# 05pwr_input.net
KiCad netlist of a schematic drawn in Altium Designer
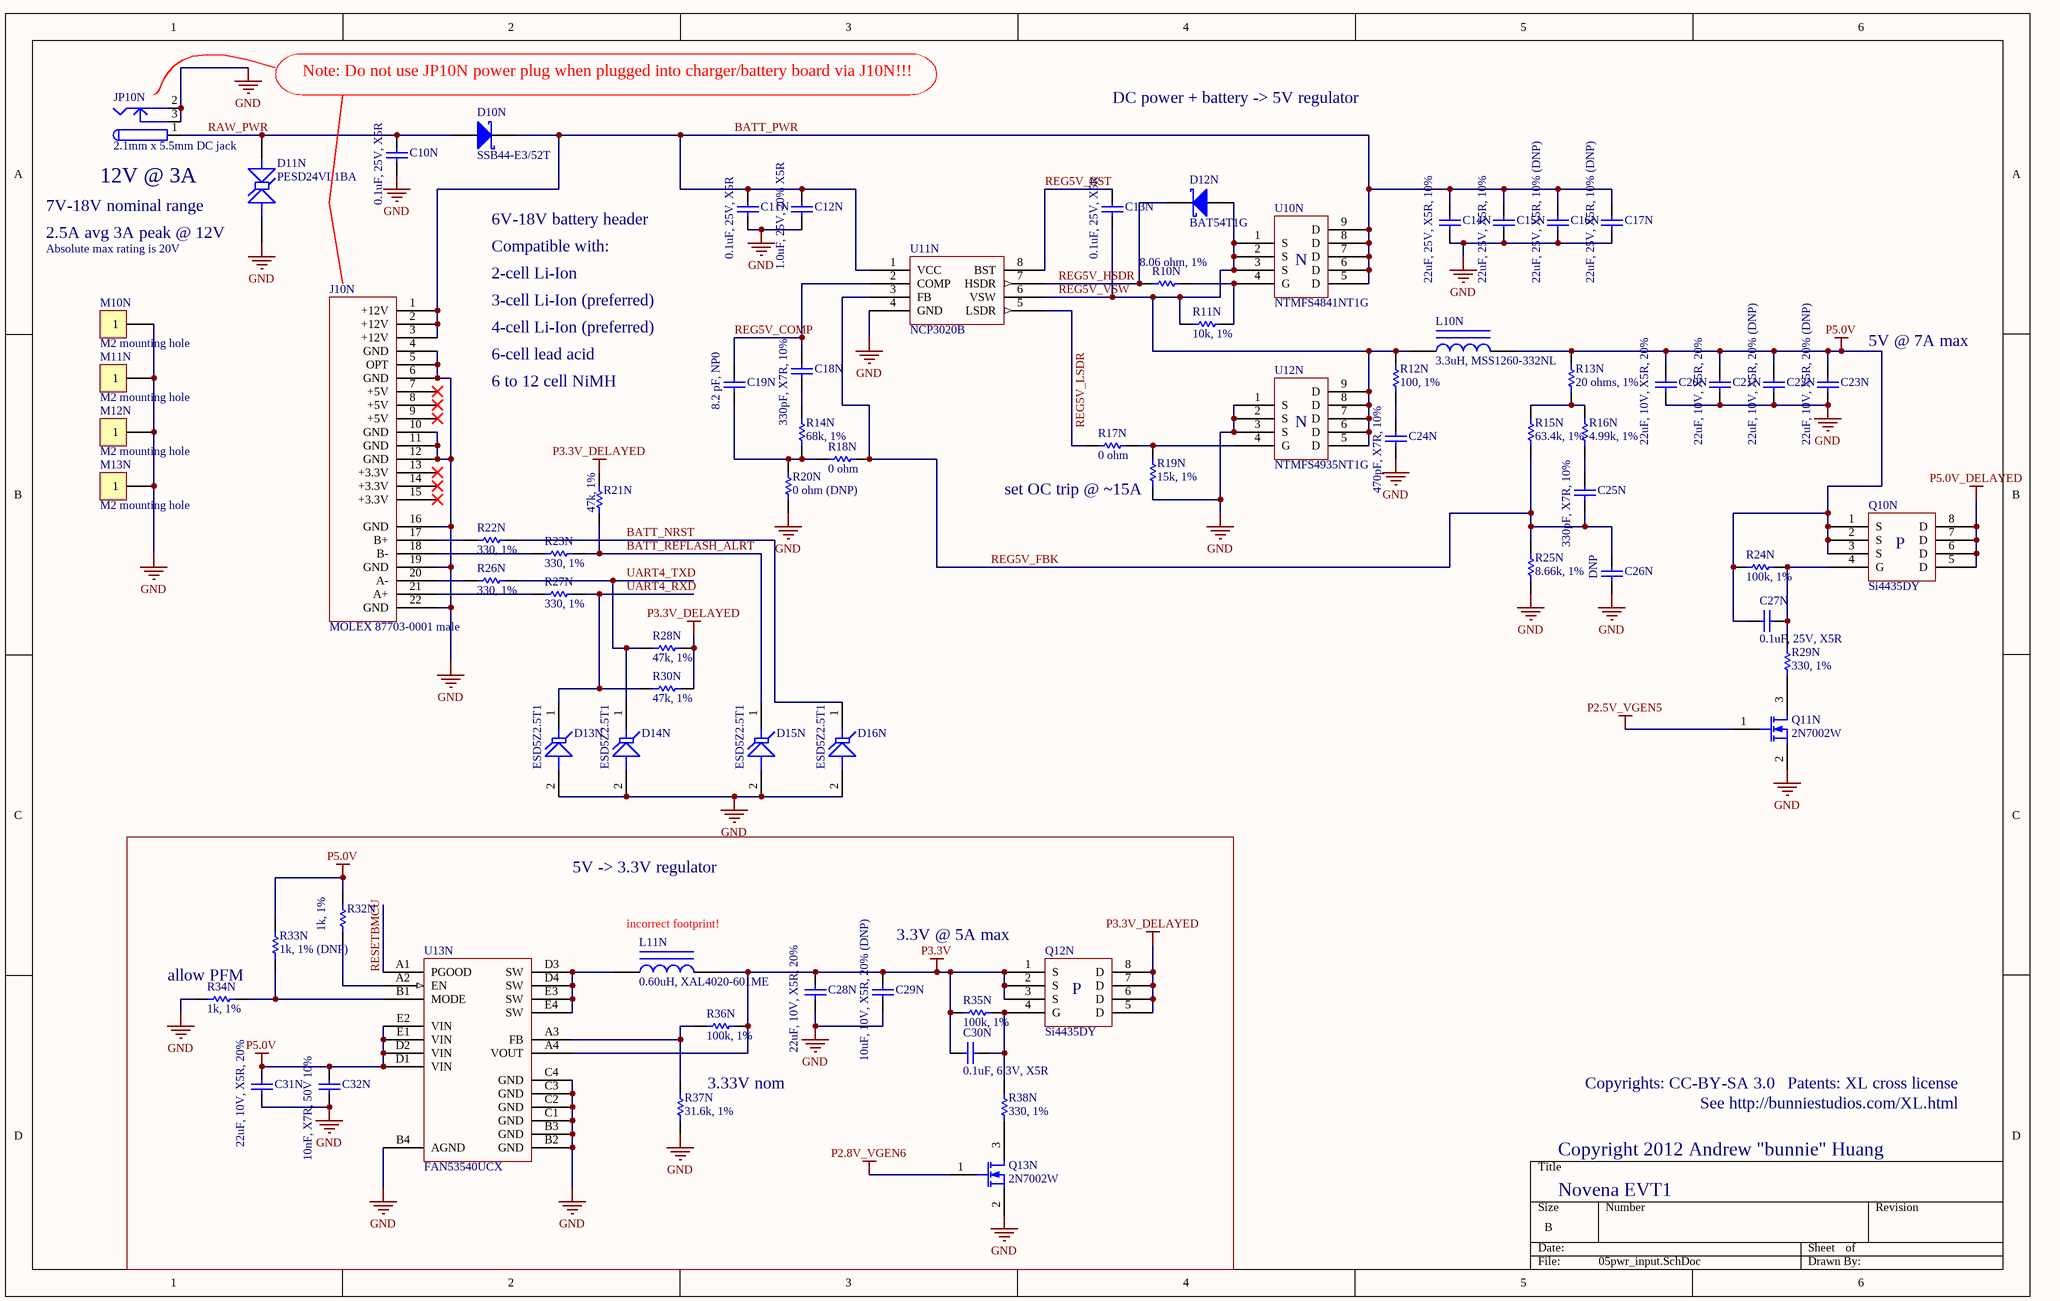
[diagram p0: 05pwr_input.SchDoc]

(export (version "E")
  (design (tool "Eeschema 10.0.6"))
  (components
    (comp (ref "C10N")
      (value "0.1uF, 25V, X5R")
      (footprint "CAPC1005N")
      (description "Capacitor (Semiconductor SIM Model)")
      (fields (field (name "PUBLISHER") "Altium Limited"))
      (libsource (lib "Miscellaneous Devices") (part "Cap Semi"))
    )
    (comp (ref "C11N")
      (value "0.1uF, 25V, X5R")
      (footprint "CAPC1005N")
      (description "Capacitor (Semiconductor SIM Model)")
      (fields (field (name "PUBLISHER") "Altium Limited"))
      (libsource (lib "Miscellaneous Devices") (part "Cap Semi"))
    )
    (comp (ref "C12N")
      (value "1.0uF, 25V, 20% X5R")
      (footprint "CAPC1608N")
      (description "Capacitor (Semiconductor SIM Model)")
      (fields (field (name "PUBLISHER") "Altium Limited"))
      (libsource (lib "Miscellaneous Devices") (part "Cap Semi"))
    )
    (comp (ref "C13N")
      (value "0.1uF, 25V, X5R")
      (footprint "CAPC1005N")
      (description "Capacitor (Semiconductor SIM Model)")
      (fields (field (name "PUBLISHER") "Altium Limited"))
      (libsource (lib "Miscellaneous Devices") (part "Cap Semi"))
    )
    (comp (ref "C14N")
      (value "22uF, 25V, X5R, 10%")
      (footprint "CAPC3225N")
      (description "Capacitor (Semiconductor SIM Model)")
      (fields (field (name "PUBLISHER") "Altium Limited"))
      (libsource (lib "Miscellaneous Devices") (part "Cap Semi"))
    )
    (comp (ref "C15N")
      (value "22uF, 25V, X5R, 10%")
      (footprint "CAPC3225N")
      (description "Capacitor (Semiconductor SIM Model)")
      (fields (field (name "PUBLISHER") "Altium Limited"))
      (libsource (lib "Miscellaneous Devices") (part "Cap Semi"))
    )
    (comp (ref "C16N")
      (value "22uF, 25V, X5R, 10% (DNP)")
      (footprint "CAPC3225N")
      (description "Capacitor (Semiconductor SIM Model)")
      (fields (field (name "PUBLISHER") "Altium Limited"))
      (libsource (lib "Miscellaneous Devices") (part "Cap Semi"))
    )
    (comp (ref "C17N")
      (value "22uF, 25V, X5R, 10% (DNP)")
      (footprint "CAPC3225N")
      (description "Capacitor (Semiconductor SIM Model)")
      (fields (field (name "PUBLISHER") "Altium Limited"))
      (libsource (lib "Miscellaneous Devices") (part "Cap Semi"))
    )
    (comp (ref "C18N")
      (value "330pF, X7R, 10%")
      (footprint "CAPC1005N")
      (description "Capacitor (Semiconductor SIM Model)")
      (fields (field (name "PUBLISHER") "Altium Limited"))
      (libsource (lib "Miscellaneous Devices") (part "Cap Semi"))
    )
    (comp (ref "C19N")
      (value "8.2 pF, NP0")
      (footprint "CAPC1005N")
      (description "Capacitor (Semiconductor SIM Model)")
      (fields (field (name "PUBLISHER") "Altium Limited"))
      (libsource (lib "Miscellaneous Devices") (part "Cap Semi"))
    )
    (comp (ref "C20N")
      (value "22uF, 10V, X5R, 20%")
      (footprint "CAPC2012N")
      (description "Capacitor (Semiconductor SIM Model)")
      (fields (field (name "PUBLISHER") "Altium Limited"))
      (libsource (lib "Miscellaneous Devices") (part "Cap Semi"))
    )
    (comp (ref "C21N")
      (value "22uF, 10V, X5R, 20%")
      (footprint "CAPC2012N")
      (description "Capacitor (Semiconductor SIM Model)")
      (fields (field (name "PUBLISHER") "Altium Limited"))
      (libsource (lib "Miscellaneous Devices") (part "Cap Semi"))
    )
    (comp (ref "C22N")
      (value "22uF, 10V, X5R, 20% (DNP)")
      (footprint "CAPC2012N")
      (description "Capacitor (Semiconductor SIM Model)")
      (fields (field (name "PUBLISHER") "Altium Limited"))
      (libsource (lib "Miscellaneous Devices") (part "Cap Semi"))
    )
    (comp (ref "C23N")
      (value "22uF, 10V, X5R, 20% (DNP)")
      (footprint "CAPC2012N")
      (description "Capacitor (Semiconductor SIM Model)")
      (fields (field (name "PUBLISHER") "Altium Limited"))
      (libsource (lib "Miscellaneous Devices") (part "Cap Semi"))
    )
    (comp (ref "C24N")
      (value "470pF, X7R, 10%")
      (footprint "CAPC1005N")
      (description "Capacitor (Semiconductor SIM Model)")
      (fields (field (name "PUBLISHER") "Altium Limited"))
      (libsource (lib "Miscellaneous Devices") (part "Cap Semi"))
    )
    (comp (ref "C25N")
      (value "330pF, X7R, 10%")
      (footprint "CAPC1005N")
      (description "Capacitor (Semiconductor SIM Model)")
      (fields (field (name "PUBLISHER") "Altium Limited"))
      (libsource (lib "Miscellaneous Devices") (part "Cap Semi"))
    )
    (comp (ref "C26N")
      (value "DNP")
      (footprint "CAPC1005N")
      (description "Capacitor (Semiconductor SIM Model)")
      (fields (field (name "PUBLISHER") "Altium Limited"))
      (libsource (lib "Miscellaneous Devices") (part "Cap Semi"))
    )
    (comp (ref "C27N")
      (value "0.1uF, 25V, X5R")
      (footprint "CAPC1005N")
      (description "Capacitor (Semiconductor SIM Model)")
      (fields (field (name "PUBLISHER") "Altium Limited"))
      (libsource (lib "Miscellaneous Devices") (part "Cap Semi"))
    )
    (comp (ref "C28N")
      (value "22uF, 10V, X5R, 20%")
      (footprint "CAPC2012N")
      (description "Capacitor (Semiconductor SIM Model)")
      (fields (field (name "PUBLISHER") "Altium Limited"))
      (libsource (lib "Miscellaneous Devices") (part "Cap Semi"))
    )
    (comp (ref "C29N")
      (value "10uF, 10V, X5R, 20% (DNP)")
      (footprint "CAPC1608N")
      (description "Capacitor (Semiconductor SIM Model)")
      (fields (field (name "PUBLISHER") "Altium Limited"))
      (libsource (lib "Miscellaneous Devices") (part "Cap Semi"))
    )
    (comp (ref "C30N")
      (value "0.1uF, 6.3V, X5R")
      (footprint "CAPC0603N_B")
      (description "Capacitor (Semiconductor SIM Model)")
      (fields (field (name "PUBLISHER") "Altium Limited"))
      (libsource (lib "Miscellaneous Devices") (part "Cap Semi"))
    )
    (comp (ref "C31N")
      (value "22uF, 10V, X5R, 20%")
      (footprint "CAPC2012N")
      (description "Capacitor (Semiconductor SIM Model)")
      (fields (field (name "PUBLISHER") "Altium Limited"))
      (libsource (lib "Miscellaneous Devices") (part "Cap Semi"))
    )
    (comp (ref "C32N")
      (value "10nF, X7R, 50V 10%")
      (footprint "CAPC1005N")
      (description "Capacitor (Semiconductor SIM Model)")
      (fields (field (name "PUBLISHER") "Altium Limited"))
      (libsource (lib "Miscellaneous Devices") (part "Cap Semi"))
    )
    (comp (ref "D10N")
      (value "SSB44-E3/52T")
      (footprint "DSO-C2/X2.3")
      (description "Schottky Diode")
      (fields (field (name "PUBLISHER") "Altium Limited"))
      (libsource (lib "Miscellaneous Devices") (part "D Schottky"))
    )
    (comp (ref "D11N")
      (value "PESD24VL1BA")
      (footprint "SOD-323")
      (description "Bidirectional zener diode, Vz 17.1V nom")
      (libsource (lib "commonsch") (part "BIDIR_ESD"))
    )
    (comp (ref "D12N")
      (value "BAT54T1G")
      (footprint "SOD123")
      (description "Schottky Diode")
      (fields (field (name "PUBLISHER") "Altium Limited"))
      (libsource (lib "Miscellaneous Devices") (part "D Schottky"))
    )
    (comp (ref "D13N")
      (value "ESD5Z2.5T1")
      (footprint "SOD-523")
      (description "On Semi 3.3V standoff TVS diode")
      (fields (field (name "PUBLISHER") "Altium Limited"))
      (libsource (lib "Miscellaneous Devices") (part "Tranzorb"))
    )
    (comp (ref "D14N")
      (value "ESD5Z2.5T1")
      (footprint "SOD-523")
      (description "On Semi 3.3V standoff TVS diode")
      (fields (field (name "PUBLISHER") "Altium Limited"))
      (libsource (lib "Miscellaneous Devices") (part "Tranzorb"))
    )
    (comp (ref "D15N")
      (value "ESD5Z2.5T1")
      (footprint "SOD-523")
      (description "On Semi 3.3V standoff TVS diode")
      (fields (field (name "PUBLISHER") "Altium Limited"))
      (libsource (lib "Miscellaneous Devices") (part "Tranzorb"))
    )
    (comp (ref "D16N")
      (value "ESD5Z2.5T1")
      (footprint "SOD-523")
      (description "On Semi 3.3V standoff TVS diode")
      (fields (field (name "PUBLISHER") "Altium Limited"))
      (libsource (lib "Miscellaneous Devices") (part "Tranzorb"))
    )
    (comp (ref "J10N")
      (value "MOLEX 87703-0001 male")
      (footprint "SATA_MOLEX-87703-0001")
      (description "SATA+Power connector")
      (libsource (lib "commonsch") (part "SATA_22P_HEADER"))
    )
    (comp (ref "JP10N")
      (value "2.1mm x 5.5mm DC jack")
      (footprint "CUI_PJ_002AH_SMT")
      (description "Low Voltage Power Supply Connector")
      (fields (field (name "PUBLISHER") "Altium Limited"))
      (libsource (lib "Miscellaneous Connectors") (part "PWR2.5"))
    )
    (comp (ref "L10N")
      (value "3.3uH, MSS1260-332NL")
      (footprint "COILCRAFT_MSS1048")
      (description "Magnetic-Core Inductor")
      (fields (field (name "PUBLISHER") "Altium Limited"))
      (libsource (lib "Miscellaneous Devices") (part "Inductor Iron"))
    )
    (comp (ref "L11N")
      (value "0.60uH, XAL4020-601ME")
      (footprint "COILCRAFT_MSS1048")
      (description "Magnetic-Core Inductor")
      (fields (field (name "PUBLISHER") "Altium Limited"))
      (libsource (lib "Miscellaneous Devices") (part "Inductor Iron"))
    )
    (comp (ref "M10N")
      (value "M2 mounting hole")
      (footprint "HOLE_M2_MOUNT")
      (description "Connector")
      (libsource (lib "*") (part "CON1"))
    )
    (comp (ref "M11N")
      (value "M2 mounting hole")
      (footprint "HOLE_M2_MOUNT")
      (description "Connector")
      (libsource (lib "*") (part "CON1"))
    )
    (comp (ref "M12N")
      (value "M2 mounting hole")
      (footprint "HOLE_M2_MOUNT")
      (description "Connector")
      (libsource (lib "*") (part "CON1"))
    )
    (comp (ref "M13N")
      (value "M2 mounting hole")
      (footprint "HOLE_M2_MOUNT")
      (description "Connector")
      (libsource (lib "*") (part "CON1"))
    )
    (comp (ref "Q10N")
      (value "Si4435DY")
      (footprint "SOIC127P600-8AN")
      (description "Singre P-channel FET, 8A, 30V")
      (libsource (lib "commonsch") (part "Si4435DY"))
    )
    (comp (ref "Q11N")
      (value "2N7002W")
      (footprint "SOT323-3AN")
      (description "N-Channel MOSFET")
      (fields (field (name "PUBLISHER") "Altium Limited"))
      (libsource (lib "Miscellaneous Devices") (part "MOSFET-N"))
    )
    (comp (ref "Q12N")
      (value "Si4435DY")
      (footprint "SOIC127P600-8AN")
      (description "Singre P-channel FET, 8A, 30V")
      (libsource (lib "commonsch") (part "Si4435DY"))
    )
    (comp (ref "Q13N")
      (value "2N7002W")
      (footprint "SOT323-3AN")
      (description "N-Channel MOSFET")
      (fields (field (name "PUBLISHER") "Altium Limited"))
      (libsource (lib "Miscellaneous Devices") (part "MOSFET-N"))
    )
    (comp (ref "R10N")
      (value "8.06 ohm, 1%")
      (footprint "RESC1005N")
      (description "Resistor")
      (fields (field (name "PUBLISHER") "Altium Limited"))
      (libsource (lib "Miscellaneous Devices") (part "Res1"))
    )
    (comp (ref "R11N")
      (value "10k, 1%")
      (footprint "RESC1005N")
      (description "Resistor")
      (fields (field (name "PUBLISHER") "Altium Limited"))
      (libsource (lib "Miscellaneous Devices") (part "Res1"))
    )
    (comp (ref "R12N")
      (value "100, 1%")
      (footprint "RESC1005N")
      (description "Resistor")
      (fields (field (name "PUBLISHER") "Altium Limited"))
      (libsource (lib "Miscellaneous Devices") (part "Res1"))
    )
    (comp (ref "R13N")
      (value "20 ohms, 1%")
      (footprint "RESC1005N")
      (description "Resistor")
      (fields (field (name "PUBLISHER") "Altium Limited"))
      (libsource (lib "Miscellaneous Devices") (part "Res1"))
    )
    (comp (ref "R14N")
      (value "68k, 1%")
      (footprint "RESC1005N")
      (description "Resistor")
      (fields (field (name "PUBLISHER") "Altium Limited"))
      (libsource (lib "Miscellaneous Devices") (part "Res1"))
    )
    (comp (ref "R15N")
      (value "63.4k, 1%")
      (footprint "RESC1005N")
      (description "Resistor")
      (fields (field (name "PUBLISHER") "Altium Limited"))
      (libsource (lib "Miscellaneous Devices") (part "Res1"))
    )
    (comp (ref "R16N")
      (value "4.99k, 1%")
      (footprint "RESC1005N")
      (description "Resistor")
      (fields (field (name "PUBLISHER") "Altium Limited"))
      (libsource (lib "Miscellaneous Devices") (part "Res1"))
    )
    (comp (ref "R17N")
      (value "0 ohm")
      (footprint "RESC1005N")
      (description "Resistor")
      (fields (field (name "PUBLISHER") "Altium Limited"))
      (libsource (lib "Miscellaneous Devices") (part "Res1"))
    )
    (comp (ref "R18N")
      (value "0 ohm")
      (footprint "RESC1005N")
      (description "Resistor")
      (fields (field (name "PUBLISHER") "Altium Limited"))
      (libsource (lib "Miscellaneous Devices") (part "Res1"))
    )
    (comp (ref "R19N")
      (value "15k, 1%")
      (footprint "RESC1005N")
      (description "Resistor")
      (fields (field (name "PUBLISHER") "Altium Limited"))
      (libsource (lib "Miscellaneous Devices") (part "Res1"))
    )
    (comp (ref "R20N")
      (value "0 ohm (DNP)")
      (footprint "RESC1005N")
      (description "Resistor")
      (fields (field (name "PUBLISHER") "Altium Limited"))
      (libsource (lib "Miscellaneous Devices") (part "Res1"))
    )
    (comp (ref "R21N")
      (value "47k, 1%")
      (footprint "RESC1005N")
      (description "Resistor")
      (fields (field (name "PUBLISHER") "Altium Limited"))
      (libsource (lib "Miscellaneous Devices") (part "Res1"))
    )
    (comp (ref "R22N")
      (value "330, 1%")
      (footprint "RESC1005N")
      (description "Resistor")
      (fields (field (name "PUBLISHER") "Altium Limited"))
      (libsource (lib "Miscellaneous Devices") (part "Res1"))
    )
    (comp (ref "R23N")
      (value "330, 1%")
      (footprint "RESC1005N")
      (description "Resistor")
      (fields (field (name "PUBLISHER") "Altium Limited"))
      (libsource (lib "Miscellaneous Devices") (part "Res1"))
    )
    (comp (ref "R24N")
      (value "100k, 1%")
      (footprint "RESC1005N")
      (description "Resistor")
      (fields (field (name "PUBLISHER") "Altium Limited"))
      (libsource (lib "Miscellaneous Devices") (part "Res1"))
    )
    (comp (ref "R25N")
      (value "8.66k, 1%")
      (footprint "RESC1005N")
      (description "Resistor")
      (fields (field (name "PUBLISHER") "Altium Limited"))
      (libsource (lib "Miscellaneous Devices") (part "Res1"))
    )
    (comp (ref "R26N")
      (value "330, 1%")
      (footprint "RESC1005N")
      (description "Resistor")
      (fields (field (name "PUBLISHER") "Altium Limited"))
      (libsource (lib "Miscellaneous Devices") (part "Res1"))
    )
    (comp (ref "R27N")
      (value "330, 1%")
      (footprint "RESC1005N")
      (description "Resistor")
      (fields (field (name "PUBLISHER") "Altium Limited"))
      (libsource (lib "Miscellaneous Devices") (part "Res1"))
    )
    (comp (ref "R28N")
      (value "47k, 1%")
      (footprint "RESC1005N")
      (description "Resistor")
      (fields (field (name "PUBLISHER") "Altium Limited"))
      (libsource (lib "Miscellaneous Devices") (part "Res1"))
    )
    (comp (ref "R29N")
      (value "330, 1%")
      (footprint "RESC1005N")
      (description "Resistor")
      (fields (field (name "PUBLISHER") "Altium Limited"))
      (libsource (lib "Miscellaneous Devices") (part "Res1"))
    )
    (comp (ref "R30N")
      (value "47k, 1%")
      (footprint "RESC1005N")
      (description "Resistor")
      (fields (field (name "PUBLISHER") "Altium Limited"))
      (libsource (lib "Miscellaneous Devices") (part "Res1"))
    )
    (comp (ref "R32N")
      (value "1k, 1%")
      (footprint "RESC1005N")
      (description "Resistor")
      (fields (field (name "PUBLISHER") "Altium Limited"))
      (libsource (lib "Miscellaneous Devices") (part "Res1"))
    )
    (comp (ref "R33N")
      (value "1k, 1% (DNP)")
      (footprint "RESC1005N")
      (description "Resistor")
      (fields (field (name "PUBLISHER") "Altium Limited"))
      (libsource (lib "Miscellaneous Devices") (part "Res1"))
    )
    (comp (ref "R34N")
      (value "1k, 1%")
      (footprint "RESC1005N")
      (description "Resistor")
      (fields (field (name "PUBLISHER") "Altium Limited"))
      (libsource (lib "Miscellaneous Devices") (part "Res1"))
    )
    (comp (ref "R35N")
      (value "100k, 1%")
      (footprint "RESC1005N")
      (description "Resistor")
      (fields (field (name "PUBLISHER") "Altium Limited"))
      (libsource (lib "Miscellaneous Devices") (part "Res1"))
    )
    (comp (ref "R36N")
      (value "100k, 1%")
      (footprint "RESC1005N")
      (description "Resistor")
      (fields (field (name "PUBLISHER") "Altium Limited"))
      (libsource (lib "Miscellaneous Devices") (part "Res1"))
    )
    (comp (ref "R37N")
      (value "31.6k, 1%")
      (footprint "RESC1005N")
      (description "Resistor")
      (fields (field (name "PUBLISHER") "Altium Limited"))
      (libsource (lib "Miscellaneous Devices") (part "Res1"))
    )
    (comp (ref "R38N")
      (value "330, 1%")
      (footprint "RESC1005N")
      (description "Resistor")
      (fields (field (name "PUBLISHER") "Altium Limited"))
      (libsource (lib "Miscellaneous Devices") (part "Res1"))
    )
    (comp (ref "U10N")
      (value "NTMFS4841NT1G")
      (footprint "ONSEMI_DFN5_5x6_1.27P")
      (description "N channel power MOSFET, 30V, 57A SO-8FL")
      (libsource (lib "commonsch") (part "NTMFS4841N"))
    )
    (comp (ref "U11N")
      (value "NCP3020B")
      (footprint "SOIC127P600-8AN")
      (description "Synchronous PWM controller, 4.7-28V in, 0.6V ref")
      (libsource (lib "commonsch") (part "NCP3020B"))
    )
    (comp (ref "U12N")
      (value "NTMFS4935NT1G")
      (footprint "ONSEMI_DFN5_5x6_1.27P")
      (description "N channel power MOSFET, 30V, 57A SO-8FL")
      (libsource (lib "commonsch") (part "NTMFS4841N"))
    )
    (comp (ref "U13N")
      (value "FAN53540UCX")
      (footprint "FAIRCHILD_WLCSP_BGA100P9X9-81A")
      (description "2.4MHz 5A Sync buck regulator, integrated FET")
      (libsource (lib "commonsch") (part "FAN53540UCX"))
    )
  )
  (nets
    (net (code "1") (name "/BATT_NRST") (class "Default")
      (node (ref "D16N") (pin "1") (pinfunction "K_1") (pintype "passive"))
      (node (ref "R22N") (pin "2") (pinfunction "2_2") (pintype "passive"))
    )
    (net (code "2") (name "/BATT_PWR") (class "Default")
      (node (ref "C11N") (pin "1") (pinfunction "1_1") (pintype "passive"))
      (node (ref "C12N") (pin "1") (pinfunction "1_1") (pintype "passive"))
      (node (ref "C14N") (pin "1") (pinfunction "1_1") (pintype "passive"))
      (node (ref "C15N") (pin "1") (pinfunction "1_1") (pintype "passive"))
      (node (ref "C16N") (pin "1") (pinfunction "1_1") (pintype "passive"))
      (node (ref "C17N") (pin "1") (pinfunction "1_1") (pintype "passive"))
      (node (ref "D10N") (pin "2") (pinfunction "K_2") (pintype "passive"))
      (node (ref "J10N") (pin "1") (pinfunction "+12V_1") (pintype "power_in"))
      (node (ref "J10N") (pin "2") (pinfunction "+12V_2") (pintype "power_in"))
      (node (ref "J10N") (pin "3") (pinfunction "+12V_3") (pintype "power_in"))
      (node (ref "U10N") (pin "5") (pinfunction "D_5") (pintype "passive"))
      (node (ref "U10N") (pin "6") (pinfunction "D_6") (pintype "passive"))
      (node (ref "U10N") (pin "7") (pinfunction "D_7") (pintype "passive"))
      (node (ref "U10N") (pin "8") (pinfunction "D_8") (pintype "passive"))
      (node (ref "U10N") (pin "9") (pinfunction "D_9") (pintype "passive"))
      (node (ref "U11N") (pin "1") (pinfunction "VCC_1") (pintype "power_in"))
    )
    (net (code "3") (name "/BATT_REFLASH_ALRT") (class "Default")
      (node (ref "D15N") (pin "1") (pinfunction "K_1") (pintype "passive"))
      (node (ref "R21N") (pin "1") (pinfunction "1_1") (pintype "passive"))
      (node (ref "R23N") (pin "2") (pinfunction "2_2") (pintype "passive"))
    )
    (net (code "4") (name "/RAW_PWR") (class "Default")
      (node (ref "C10N") (pin "1") (pinfunction "1_1") (pintype "passive"))
      (node (ref "D10N") (pin "1") (pinfunction "A_1") (pintype "passive"))
      (node (ref "D11N") (pin "2") (pinfunction "K_2") (pintype "passive"))
      (node (ref "JP10N") (pin "1") (pintype "power_in"))
    )
    (net (code "5") (name "/REG5V_BST") (class "Default")
      (node (ref "C13N") (pin "1") (pinfunction "1_1") (pintype "passive"))
      (node (ref "U11N") (pin "8") (pinfunction "BST_8") (pintype "passive"))
    )
    (net (code "6") (name "/REG5V_COMP") (class "Default")
      (node (ref "C18N") (pin "1") (pinfunction "1_1") (pintype "passive"))
      (node (ref "C19N") (pin "1") (pinfunction "1_1") (pintype "passive"))
      (node (ref "U11N") (pin "2") (pinfunction "COMP_2") (pintype "passive"))
    )
    (net (code "7") (name "/REG5V_FBK") (class "Default")
      (node (ref "C25N") (pin "2") (pinfunction "2_2") (pintype "passive"))
      (node (ref "C26N") (pin "1") (pinfunction "1_1") (pintype "passive"))
      (node (ref "R15N") (pin "1") (pinfunction "1_1") (pintype "passive"))
      (node (ref "R18N") (pin "2") (pinfunction "2_2") (pintype "passive"))
      (node (ref "R25N") (pin "2") (pinfunction "2_2") (pintype "passive"))
      (node (ref "U11N") (pin "3") (pinfunction "FB_3") (pintype "passive"))
    )
    (net (code "8") (name "/REG5V_HSDR") (class "Default")
      (node (ref "D12N") (pin "2") (pinfunction "K_2") (pintype "passive"))
      (node (ref "R10N") (pin "1") (pinfunction "1_1") (pintype "passive"))
      (node (ref "U11N") (pin "7") (pinfunction "HSDR_7") (pintype "output"))
    )
    (net (code "9") (name "/REG5V_LSDR") (class "Default")
      (node (ref "R17N") (pin "1") (pinfunction "1_1") (pintype "passive"))
      (node (ref "U11N") (pin "5") (pinfunction "LSDR_5") (pintype "output"))
    )
    (net (code "10") (name "/REG5V_VSW") (class "Default")
      (node (ref "C13N") (pin "2") (pinfunction "2_2") (pintype "passive"))
      (node (ref "D12N") (pin "1") (pinfunction "A_1") (pintype "passive"))
      (node (ref "L10N") (pin "1") (pinfunction "1_1") (pintype "passive"))
      (node (ref "R11N") (pin "2") (pinfunction "2_2") (pintype "passive"))
      (node (ref "R12N") (pin "2") (pinfunction "2_2") (pintype "passive"))
      (node (ref "U10N") (pin "1") (pinfunction "S_1") (pintype "passive"))
      (node (ref "U10N") (pin "2") (pinfunction "S_2") (pintype "passive"))
      (node (ref "U10N") (pin "3") (pinfunction "S_3") (pintype "passive"))
      (node (ref "U11N") (pin "6") (pinfunction "VSW_6") (pintype "passive"))
      (node (ref "U12N") (pin "5") (pinfunction "D_5") (pintype "passive"))
      (node (ref "U12N") (pin "6") (pinfunction "D_6") (pintype "passive"))
      (node (ref "U12N") (pin "7") (pinfunction "D_7") (pintype "passive"))
      (node (ref "U12N") (pin "8") (pinfunction "D_8") (pintype "passive"))
      (node (ref "U12N") (pin "9") (pinfunction "D_9") (pintype "passive"))
    )
    (net (code "11") (name "/RESETBMCU") (class "Default")
      (node (ref "U13N") (pin "A1") (pinfunction "PGOOD_A1") (pintype "open_collector"))
    )
    (net (code "12") (name "/UART4_RXD") (class "Default")
      (node (ref "D13N") (pin "1") (pinfunction "K_1") (pintype "passive"))
      (node (ref "R27N") (pin "2") (pinfunction "2_2") (pintype "passive"))
      (node (ref "R30N") (pin "2") (pinfunction "2_2") (pintype "passive"))
    )
    (net (code "13") (name "/UART4_TXD") (class "Default")
      (node (ref "D14N") (pin "1") (pinfunction "K_1") (pintype "passive"))
      (node (ref "R26N") (pin "2") (pinfunction "2_2") (pintype "passive"))
      (node (ref "R28N") (pin "2") (pinfunction "2_2") (pintype "passive"))
    )
    (net (code "14") (name "GND") (class "Default")
      (node (ref "C10N") (pin "2") (pinfunction "2_2") (pintype "passive"))
      (node (ref "C11N") (pin "2") (pinfunction "2_2") (pintype "passive"))
      (node (ref "C12N") (pin "2") (pinfunction "2_2") (pintype "passive"))
      (node (ref "C14N") (pin "2") (pinfunction "2_2") (pintype "passive"))
      (node (ref "C15N") (pin "2") (pinfunction "2_2") (pintype "passive"))
      (node (ref "C16N") (pin "2") (pinfunction "2_2") (pintype "passive"))
      (node (ref "C17N") (pin "2") (pinfunction "2_2") (pintype "passive"))
      (node (ref "C20N") (pin "2") (pinfunction "2_2") (pintype "passive"))
      (node (ref "C21N") (pin "2") (pinfunction "2_2") (pintype "passive"))
      (node (ref "C22N") (pin "2") (pinfunction "2_2") (pintype "passive"))
      (node (ref "C23N") (pin "2") (pinfunction "2_2") (pintype "passive"))
      (node (ref "C24N") (pin "2") (pinfunction "2_2") (pintype "passive"))
      (node (ref "C26N") (pin "2") (pinfunction "2_2") (pintype "passive"))
      (node (ref "C28N") (pin "2") (pinfunction "2_2") (pintype "passive"))
      (node (ref "C29N") (pin "2") (pinfunction "2_2") (pintype "passive"))
      (node (ref "C31N") (pin "2") (pinfunction "2_2") (pintype "passive"))
      (node (ref "C32N") (pin "2") (pinfunction "2_2") (pintype "passive"))
      (node (ref "D11N") (pin "1") (pinfunction "A_1") (pintype "passive"))
      (node (ref "D13N") (pin "2") (pinfunction "A_2") (pintype "passive"))
      (node (ref "D14N") (pin "2") (pinfunction "A_2") (pintype "passive"))
      (node (ref "D15N") (pin "2") (pinfunction "A_2") (pintype "passive"))
      (node (ref "D16N") (pin "2") (pinfunction "A_2") (pintype "passive"))
      (node (ref "J10N") (pin "10") (pinfunction "GND_10") (pintype "power_in"))
      (node (ref "J10N") (pin "11") (pinfunction "GND_11") (pintype "power_in"))
      (node (ref "J10N") (pin "12") (pinfunction "GND_12") (pintype "power_in"))
      (node (ref "J10N") (pin "16") (pinfunction "GND_16") (pintype "power_in"))
      (node (ref "J10N") (pin "19") (pinfunction "GND_19") (pintype "power_in"))
      (node (ref "J10N") (pin "22") (pinfunction "GND_22") (pintype "power_in"))
      (node (ref "J10N") (pin "4") (pinfunction "GND_4") (pintype "power_in"))
      (node (ref "J10N") (pin "5") (pinfunction "OPT_5") (pintype "passive"))
      (node (ref "J10N") (pin "6") (pinfunction "GND_6") (pintype "power_in"))
      (node (ref "JP10N") (pin "2") (pintype "power_in"))
      (node (ref "JP10N") (pin "3") (pintype "power_in"))
      (node (ref "M10N") (pin "1") (pinfunction "1_1") (pintype "passive"))
      (node (ref "M11N") (pin "1") (pinfunction "1_1") (pintype "passive"))
      (node (ref "M12N") (pin "1") (pinfunction "1_1") (pintype "passive"))
      (node (ref "M13N") (pin "1") (pinfunction "1_1") (pintype "passive"))
      (node (ref "Q11N") (pin "2") (pinfunction "S_2") (pintype "passive"))
      (node (ref "Q13N") (pin "2") (pinfunction "S_2") (pintype "passive"))
      (node (ref "R19N") (pin "1") (pinfunction "1_1") (pintype "passive"))
      (node (ref "R20N") (pin "1") (pinfunction "1_1") (pintype "passive"))
      (node (ref "R25N") (pin "1") (pinfunction "1_1") (pintype "passive"))
      (node (ref "R34N") (pin "2") (pinfunction "2_2") (pintype "passive"))
      (node (ref "R37N") (pin "1") (pinfunction "1_1") (pintype "passive"))
      (node (ref "U11N") (pin "4") (pinfunction "GND_4") (pintype "power_in"))
      (node (ref "U12N") (pin "1") (pinfunction "S_1") (pintype "passive"))
      (node (ref "U12N") (pin "2") (pinfunction "S_2") (pintype "passive"))
      (node (ref "U12N") (pin "3") (pinfunction "S_3") (pintype "passive"))
      (node (ref "U13N") (pin "B2") (pinfunction "GND_B2") (pintype "power_in"))
      (node (ref "U13N") (pin "B3") (pinfunction "GND_B3") (pintype "power_in"))
      (node (ref "U13N") (pin "B4") (pinfunction "AGND_B4") (pintype "power_in"))
      (node (ref "U13N") (pin "C1") (pinfunction "GND_C1") (pintype "power_in"))
      (node (ref "U13N") (pin "C2") (pinfunction "GND_C2") (pintype "power_in"))
      (node (ref "U13N") (pin "C3") (pinfunction "GND_C3") (pintype "power_in"))
      (node (ref "U13N") (pin "C4") (pinfunction "GND_C4") (pintype "power_in"))
    )
    (net (code "15") (name "Net-(C18N-Pad2)") (class "Default")
      (node (ref "C18N") (pin "2") (pinfunction "2_2") (pintype "passive"))
      (node (ref "R14N") (pin "2") (pinfunction "2_2") (pintype "passive"))
    )
    (net (code "16") (name "Net-(C19N-Pad2)") (class "Default")
      (node (ref "C19N") (pin "2") (pinfunction "2_2") (pintype "passive"))
      (node (ref "R14N") (pin "1") (pinfunction "1_1") (pintype "passive"))
      (node (ref "R18N") (pin "1") (pinfunction "1_1") (pintype "passive"))
      (node (ref "R20N") (pin "2") (pinfunction "2_2") (pintype "passive"))
    )
    (net (code "17") (name "Net-(C24N-Pad1)") (class "Default")
      (node (ref "C24N") (pin "1") (pinfunction "1_1") (pintype "passive"))
      (node (ref "R12N") (pin "1") (pinfunction "1_1") (pintype "passive"))
    )
    (net (code "18") (name "Net-(C25N-Pad1)") (class "Default")
      (node (ref "C25N") (pin "1") (pinfunction "1_1") (pintype "passive"))
      (node (ref "R16N") (pin "1") (pinfunction "1_1") (pintype "passive"))
    )
    (net (code "19") (name "Net-(J10N-A+)") (class "Default")
      (node (ref "J10N") (pin "21") (pinfunction "A+_21") (pintype "passive"))
      (node (ref "R27N") (pin "1") (pinfunction "1_1") (pintype "passive"))
    )
    (net (code "20") (name "Net-(J10N-A-)") (class "Default")
      (node (ref "J10N") (pin "20") (pinfunction "A-_20") (pintype "passive"))
      (node (ref "R26N") (pin "1") (pinfunction "1_1") (pintype "passive"))
    )
    (net (code "21") (name "Net-(J10N-B+)") (class "Default")
      (node (ref "J10N") (pin "17") (pinfunction "B+_17") (pintype "passive"))
      (node (ref "R22N") (pin "1") (pinfunction "1_1") (pintype "passive"))
    )
    (net (code "22") (name "Net-(J10N-B-)") (class "Default")
      (node (ref "J10N") (pin "18") (pinfunction "B-_18") (pintype "passive"))
      (node (ref "R23N") (pin "1") (pinfunction "1_1") (pintype "passive"))
    )
    (net (code "23") (name "Net-(L11N-Pad1)") (class "Default")
      (node (ref "L11N") (pin "1") (pinfunction "1_1") (pintype "passive"))
      (node (ref "U13N") (pin "D3") (pinfunction "SW_D3") (pintype "passive"))
      (node (ref "U13N") (pin "D4") (pinfunction "SW_D4") (pintype "passive"))
      (node (ref "U13N") (pin "E3") (pinfunction "SW_E3") (pintype "passive"))
      (node (ref "U13N") (pin "E4") (pinfunction "SW_E4") (pintype "passive"))
    )
    (net (code "24") (name "Net-(Q10N-G)") (class "Default")
      (node (ref "C27N") (pin "2") (pinfunction "2_2") (pintype "passive"))
      (node (ref "Q10N") (pin "4") (pinfunction "G_4") (pintype "passive"))
      (node (ref "R24N") (pin "1") (pinfunction "1_1") (pintype "passive"))
      (node (ref "R29N") (pin "1") (pinfunction "1_1") (pintype "passive"))
    )
    (net (code "25") (name "Net-(Q11N-D)") (class "Default")
      (node (ref "Q11N") (pin "3") (pinfunction "D_3") (pintype "passive"))
      (node (ref "R29N") (pin "2") (pinfunction "2_2") (pintype "passive"))
    )
    (net (code "26") (name "Net-(Q12N-G)") (class "Default")
      (node (ref "C30N") (pin "2") (pinfunction "2_2") (pintype "passive"))
      (node (ref "Q12N") (pin "4") (pinfunction "G_4") (pintype "passive"))
      (node (ref "R35N") (pin "1") (pinfunction "1_1") (pintype "passive"))
      (node (ref "R38N") (pin "1") (pinfunction "1_1") (pintype "passive"))
    )
    (net (code "27") (name "Net-(Q13N-D)") (class "Default")
      (node (ref "Q13N") (pin "3") (pinfunction "D_3") (pintype "passive"))
      (node (ref "R38N") (pin "2") (pinfunction "2_2") (pintype "passive"))
    )
    (net (code "28") (name "Net-(R13N-Pad1)") (class "Default")
      (node (ref "R13N") (pin "1") (pinfunction "1_1") (pintype "passive"))
      (node (ref "R15N") (pin "2") (pinfunction "2_2") (pintype "passive"))
      (node (ref "R16N") (pin "2") (pinfunction "2_2") (pintype "passive"))
    )
    (net (code "29") (name "Net-(U10N-G)") (class "Default")
      (node (ref "R10N") (pin "2") (pinfunction "2_2") (pintype "passive"))
      (node (ref "R11N") (pin "1") (pinfunction "1_1") (pintype "passive"))
      (node (ref "U10N") (pin "4") (pinfunction "G_4") (pintype "passive"))
    )
    (net (code "30") (name "Net-(U12N-G)") (class "Default")
      (node (ref "R17N") (pin "2") (pinfunction "2_2") (pintype "passive"))
      (node (ref "R19N") (pin "2") (pinfunction "2_2") (pintype "passive"))
      (node (ref "U12N") (pin "4") (pinfunction "G_4") (pintype "passive"))
    )
    (net (code "31") (name "Net-(U13N-EN)") (class "Default")
      (node (ref "R32N") (pin "2") (pinfunction "2_2") (pintype "passive"))
      (node (ref "U13N") (pin "A2") (pinfunction "EN_A2") (pintype "input"))
    )
    (net (code "32") (name "Net-(U13N-FB)") (class "Default")
      (node (ref "R36N") (pin "2") (pinfunction "2_2") (pintype "passive"))
      (node (ref "R37N") (pin "2") (pinfunction "2_2") (pintype "passive"))
      (node (ref "U13N") (pin "A3") (pinfunction "FB_A3") (pintype "passive"))
    )
    (net (code "33") (name "Net-(U13N-MODE)") (class "Default")
      (node (ref "R33N") (pin "1") (pinfunction "1_1") (pintype "passive"))
      (node (ref "R34N") (pin "1") (pinfunction "1_1") (pintype "passive"))
      (node (ref "U13N") (pin "B1") (pinfunction "MODE_B1") (pintype "passive"))
    )
    (net (code "34") (name "P2.5V_VGEN5") (class "Default")
      (node (ref "Q11N") (pin "1") (pinfunction "G_1") (pintype "passive"))
    )
    (net (code "35") (name "P2.8V_VGEN6") (class "Default")
      (node (ref "Q13N") (pin "1") (pinfunction "G_1") (pintype "passive"))
    )
    (net (code "36") (name "P3.3V") (class "Default")
      (node (ref "C28N") (pin "1") (pinfunction "1_1") (pintype "passive"))
      (node (ref "C29N") (pin "1") (pinfunction "1_1") (pintype "passive"))
      (node (ref "C30N") (pin "1") (pinfunction "1_1") (pintype "passive"))
      (node (ref "L11N") (pin "2") (pinfunction "2_2") (pintype "passive"))
      (node (ref "Q12N") (pin "1") (pinfunction "S_1") (pintype "passive"))
      (node (ref "Q12N") (pin "2") (pinfunction "S_2") (pintype "passive"))
      (node (ref "Q12N") (pin "3") (pinfunction "S_3") (pintype "passive"))
      (node (ref "R35N") (pin "2") (pinfunction "2_2") (pintype "passive"))
      (node (ref "R36N") (pin "1") (pinfunction "1_1") (pintype "passive"))
      (node (ref "U13N") (pin "A4") (pinfunction "VOUT_A4") (pintype "passive"))
    )
    (net (code "37") (name "P3.3V_DELAYED") (class "Default")
      (node (ref "Q12N") (pin "5") (pinfunction "D_5") (pintype "passive"))
      (node (ref "Q12N") (pin "6") (pinfunction "D_6") (pintype "passive"))
      (node (ref "Q12N") (pin "7") (pinfunction "D_7") (pintype "passive"))
      (node (ref "Q12N") (pin "8") (pinfunction "D_8") (pintype "passive"))
      (node (ref "R21N") (pin "2") (pinfunction "2_2") (pintype "passive"))
      (node (ref "R28N") (pin "1") (pinfunction "1_1") (pintype "passive"))
      (node (ref "R30N") (pin "1") (pinfunction "1_1") (pintype "passive"))
    )
    (net (code "38") (name "P5.0V") (class "Default")
      (node (ref "C20N") (pin "1") (pinfunction "1_1") (pintype "passive"))
      (node (ref "C21N") (pin "1") (pinfunction "1_1") (pintype "passive"))
      (node (ref "C22N") (pin "1") (pinfunction "1_1") (pintype "passive"))
      (node (ref "C23N") (pin "1") (pinfunction "1_1") (pintype "passive"))
      (node (ref "C27N") (pin "1") (pinfunction "1_1") (pintype "passive"))
      (node (ref "C31N") (pin "1") (pinfunction "1_1") (pintype "passive"))
      (node (ref "C32N") (pin "1") (pinfunction "1_1") (pintype "passive"))
      (node (ref "L10N") (pin "2") (pinfunction "2_2") (pintype "passive"))
      (node (ref "Q10N") (pin "1") (pinfunction "S_1") (pintype "passive"))
      (node (ref "Q10N") (pin "2") (pinfunction "S_2") (pintype "passive"))
      (node (ref "Q10N") (pin "3") (pinfunction "S_3") (pintype "passive"))
      (node (ref "R13N") (pin "2") (pinfunction "2_2") (pintype "passive"))
      (node (ref "R24N") (pin "2") (pinfunction "2_2") (pintype "passive"))
      (node (ref "R32N") (pin "1") (pinfunction "1_1") (pintype "passive"))
      (node (ref "R33N") (pin "2") (pinfunction "2_2") (pintype "passive"))
      (node (ref "U13N") (pin "D1") (pinfunction "VIN_D1") (pintype "power_in"))
      (node (ref "U13N") (pin "D2") (pinfunction "VIN_D2") (pintype "power_in"))
      (node (ref "U13N") (pin "E1") (pinfunction "VIN_E1") (pintype "power_in"))
      (node (ref "U13N") (pin "E2") (pinfunction "VIN_E2") (pintype "power_in"))
    )
    (net (code "39") (name "P5.0V_DELAYED") (class "Default")
      (node (ref "Q10N") (pin "5") (pinfunction "D_5") (pintype "passive"))
      (node (ref "Q10N") (pin "6") (pinfunction "D_6") (pintype "passive"))
      (node (ref "Q10N") (pin "7") (pinfunction "D_7") (pintype "passive"))
      (node (ref "Q10N") (pin "8") (pinfunction "D_8") (pintype "passive"))
    )
    (net (code "40") (name "unconnected-(J10N-+3.3V-Pad13)") (class "Default")
      (node (ref "J10N") (pin "13") (pinfunction "+3.3V_13") (pintype "power_in+no_connect"))
    )
    (net (code "41") (name "unconnected-(J10N-+3.3V-Pad14)") (class "Default")
      (node (ref "J10N") (pin "14") (pinfunction "+3.3V_14") (pintype "power_in+no_connect"))
    )
    (net (code "42") (name "unconnected-(J10N-+3.3V-Pad15)") (class "Default")
      (node (ref "J10N") (pin "15") (pinfunction "+3.3V_15") (pintype "power_in+no_connect"))
    )
    (net (code "43") (name "unconnected-(J10N-+5V-Pad7)") (class "Default")
      (node (ref "J10N") (pin "7") (pinfunction "+5V_7") (pintype "power_in+no_connect"))
    )
    (net (code "44") (name "unconnected-(J10N-+5V-Pad8)") (class "Default")
      (node (ref "J10N") (pin "8") (pinfunction "+5V_8") (pintype "power_in+no_connect"))
    )
    (net (code "45") (name "unconnected-(J10N-+5V-Pad9)") (class "Default")
      (node (ref "J10N") (pin "9") (pinfunction "+5V_9") (pintype "power_in+no_connect"))
    )
  )
)
